# cradle_venus.net
KiCad netlist of a schematic drawn in EAGLE
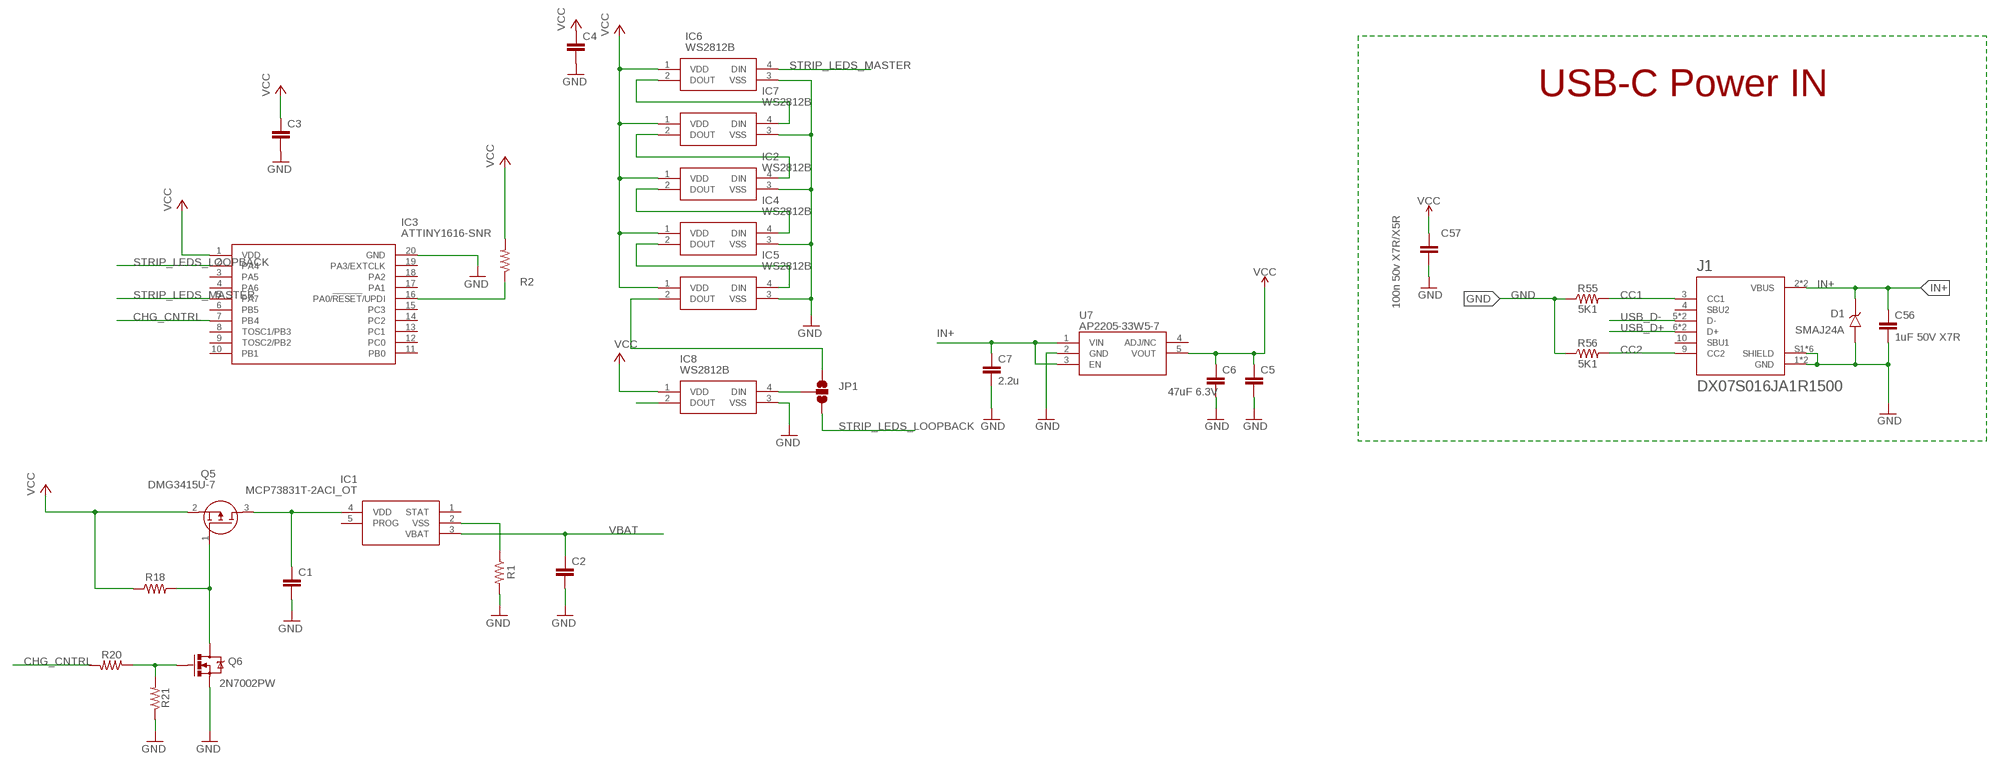
[diagram p0: schematic, sheet 1]

(export (version "E")
  (design (tool "Eeschema 10.0.6"))
  (components
    (comp (ref "C1")
      (value "C-EUC0805")
      (footprint "eagle-import:C0805")
      (libsource (lib "eagle-import") (part "C-EUC0805"))
    )
    (comp (ref "C2")
      (value "C-EUC0805")
      (footprint "eagle-import:C0805")
      (libsource (lib "eagle-import") (part "C-EUC0805"))
    )
    (comp (ref "C3")
      (value "C-EUC0805")
      (footprint "eagle-import:C0805")
      (libsource (lib "eagle-import") (part "C-EUC0805"))
    )
    (comp (ref "C4")
      (value "C-EUC0805")
      (footprint "eagle-import:C0805")
      (libsource (lib "eagle-import") (part "C-EUC0805"))
    )
    (comp (ref "C5")
      (value "C-EUC0805")
      (footprint "eagle-import:C0805")
      (libsource (lib "eagle-import") (part "C-EUC0805"))
    )
    (comp (ref "C6")
      (value "47uF 6.3V")
      (footprint "eagle-import:0603-CAP")
      (libsource (lib "eagle-import") (part "4.7UF-6.3V-10%(0603)0603"))
    )
    (comp (ref "C7")
      (value "2.2u")
      (footprint "eagle-import:0603-CAP")
      (libsource (lib "eagle-import") (part "4.7UF-6.3V-10%(0603)0603"))
    )
    (comp (ref "C56")
      (value "1uF 50V X7R")
      (footprint "eagle-import:0805")
      (libsource (lib "eagle-import") (part "CAP0805"))
    )
    (comp (ref "C57")
      (value "100n 50v X7R/X5R")
      (footprint "eagle-import:0805")
      (libsource (lib "eagle-import") (part "CAP0805"))
    )
    (comp (ref "D1")
      (value "SMAJ24A")
      (footprint "eagle-import:DIOM4325X244N")
      (fields (field (name "MF") "Micro Commercial Components") (field (name "MP") "3SMAJ5934B"))
      (libsource (lib "eagle-import") (part "3SMAJ5934B"))
    )
    (comp (ref "IC1")
      (value "MCP73831T-2ACI_OT")
      (footprint "eagle-import:SOT95P270X145-5N")
      (fields
        (field (name "ARROW_PART_NUMBER") "MCP73831T-2ACI/OT")
        (field (name "MOUSER_PART_NUMBER") "579-MCP73831T-2ACIOT")
      )
      (libsource (lib "eagle-import") (part "MCP73831T-2ACI_OT"))
    )
    (comp (ref "IC2")
      (value "WS2812B")
      (footprint "eagle-import:WS2812B")
      (libsource (lib "eagle-import") (part "WS2812B"))
    )
    (comp (ref "IC3")
      (value "ATTINY1616-SNR")
      (footprint "eagle-import:SOIC127P1030X265-20N")
      (fields (field (name "MOUSER_PART_NUMBER") "556-ATTINY1616SNR"))
      (libsource (lib "eagle-import") (part "ATTINY1616-SNR"))
    )
    (comp (ref "IC4")
      (value "WS2812B")
      (footprint "eagle-import:WS2812B")
      (libsource (lib "eagle-import") (part "WS2812B"))
    )
    (comp (ref "IC5")
      (value "WS2812B")
      (footprint "eagle-import:WS2812B")
      (libsource (lib "eagle-import") (part "WS2812B"))
    )
    (comp (ref "IC6")
      (value "WS2812B")
      (footprint "eagle-import:WS2812B")
      (libsource (lib "eagle-import") (part "WS2812B"))
    )
    (comp (ref "IC7")
      (value "WS2812B")
      (footprint "eagle-import:WS2812B")
      (libsource (lib "eagle-import") (part "WS2812B"))
    )
    (comp (ref "IC8")
      (value "WS2812B")
      (footprint "eagle-import:WS2812B")
      (libsource (lib "eagle-import") (part "WS2812B"))
    )
    (comp (ref "J1")
      (value "DX07S016JA1R1500")
      (footprint "eagle-import:JAE_DX07S016JA1R1500")
      (fields
        (field (name "DIGI-KEY_PART_NUMBER") "670-DX07S016JA1R1500CT-ND")
        (field (name "MF") "JAE Electronics")
      )
      (libsource (lib "eagle-import") (part "DX07S016JA1R1500"))
    )
    (comp (ref "JP1")
      (value "JUMPER-SMT_3_NO_SILK")
      (footprint "eagle-import:SMT-JUMPER_3_NO_SILK")
      (libsource (lib "eagle-import") (part "JUMPER-SMT_3_NO_SILK"))
    )
    (comp (ref "Q5")
      (value "DMG3415U-7")
      (footprint "eagle-import:SSM3J332RLFT")
      (fields
        (field (name "ARROW_PART_NUMBER") "SSM3J338R,LF")
        (field (name "MOUSER_PART_NUMBER") "757-SSM3J338RLF")
      )
      (libsource (lib "eagle-import") (part "SSM3J338R,LF"))
    )
    (comp (ref "Q6")
      (value "2N7002PW")
      (footprint "eagle-import:SOT323")
      (libsource (lib "eagle-import") (part "MOSFET-NCHANNEL2N7002PW"))
    )
    (comp (ref "R1")
      (value "RESISTOR0805")
      (footprint "eagle-import:0805")
      (libsource (lib "eagle-import") (part "RESISTOR0805"))
    )
    (comp (ref "R2")
      (value "RESISTOR0805")
      (footprint "eagle-import:0805")
      (libsource (lib "eagle-import") (part "RESISTOR0805"))
    )
    (comp (ref "R18")
      (value "RESISTOR0805")
      (footprint "eagle-import:0805")
      (libsource (lib "eagle-import") (part "RESISTOR0805"))
    )
    (comp (ref "R20")
      (value "RESISTOR0805")
      (footprint "eagle-import:0805")
      (libsource (lib "eagle-import") (part "RESISTOR0805"))
    )
    (comp (ref "R21")
      (value "RESISTOR0805")
      (footprint "eagle-import:0805")
      (libsource (lib "eagle-import") (part "RESISTOR0805"))
    )
    (comp (ref "R55")
      (value "5K1")
      (footprint "eagle-import:0805")
      (libsource (lib "eagle-import") (part "RESISTOR0805"))
    )
    (comp (ref "R56")
      (value "5K1")
      (footprint "eagle-import:0805")
      (libsource (lib "eagle-import") (part "RESISTOR0805"))
    )
    (comp (ref "U7")
      (value "AP2205-33W5-7")
      (footprint "eagle-import:SOT95P282X145-5N")
      (fields
        (field (name "MANUFACTURER_PART_NUMBER") "AP2205-W5-7")
        (field (name "MOUSER_PART_NUMBER") "621-AP2205-W5-7")
      )
      (libsource (lib "eagle-import") (part "AP2205-W5-7"))
    )
  )
  (nets
    (net (code "1") (name "/CC1") (class "Default")
      (node (ref "J1") (pin "3") (pinfunction "CC1_3") (pintype "passive"))
      (node (ref "R55") (pin "2") (pinfunction "2_2") (pintype "passive"))
    )
    (net (code "2") (name "/CC2") (class "Default")
      (node (ref "J1") (pin "9") (pinfunction "CC2_9") (pintype "passive"))
      (node (ref "R56") (pin "2") (pinfunction "2_2") (pintype "passive"))
    )
    (net (code "3") (name "/CHG_CNTRL") (class "Default")
      (node (ref "IC3") (pin "7") (pinfunction "PB4_7") (pintype "bidirectional"))
      (node (ref "R20") (pin "2") (pinfunction "2_2") (pintype "passive"))
    )
    (net (code "4") (name "/STRIP_LEDS_LOOPBACK") (class "Default")
      (node (ref "IC3") (pin "2") (pinfunction "PA4_2") (pintype "bidirectional"))
      (node (ref "JP1") (pin "3") (pinfunction "3_3") (pintype "passive"))
    )
    (net (code "5") (name "/STRIP_LEDS_MASTER") (class "Default")
      (node (ref "IC3") (pin "5") (pinfunction "PA7_5") (pintype "bidirectional"))
      (node (ref "IC6") (pin "4") (pinfunction "DIN_4") (pintype "bidirectional"))
    )
    (net (code "6") (name "/USB_D+") (class "Default")
      (node (ref "J1") (pin "6") (pinfunction "D+_6") (pintype "passive"))
      (node (ref "J1") (pin "7") (pinfunction "D+_7") (pintype "passive"))
    )
    (net (code "7") (name "/USB_D-") (class "Default")
      (node (ref "J1") (pin "5") (pinfunction "D-_5") (pintype "passive"))
      (node (ref "J1") (pin "8") (pinfunction "D-_8") (pintype "passive"))
    )
    (net (code "8") (name "/VBAT") (class "Default")
      (node (ref "C2") (pin "1") (pinfunction "1_1") (pintype "passive"))
      (node (ref "IC1") (pin "3") (pinfunction "VBAT_3") (pintype "bidirectional"))
    )
    (net (code "9") (name "GND") (class "Default")
      (node (ref "C1") (pin "2") (pinfunction "2_2") (pintype "passive"))
      (node (ref "C2") (pin "2") (pinfunction "2_2") (pintype "passive"))
      (node (ref "C3") (pin "2") (pinfunction "2_2") (pintype "passive"))
      (node (ref "C4") (pin "2") (pinfunction "2_2") (pintype "passive"))
      (node (ref "C5") (pin "2") (pinfunction "2_2") (pintype "passive"))
      (node (ref "C56") (pin "2") (pinfunction "2_2") (pintype "passive"))
      (node (ref "C57") (pin "2") (pinfunction "2_2") (pintype "passive"))
      (node (ref "C6") (pin "2") (pinfunction "2_2") (pintype "passive"))
      (node (ref "C7") (pin "2") (pinfunction "2_2") (pintype "passive"))
      (node (ref "D1") (pin "A") (pinfunction "A_A") (pintype "passive"))
      (node (ref "IC2") (pin "3") (pinfunction "VSS_3") (pintype "bidirectional"))
      (node (ref "IC3") (pin "20") (pinfunction "GND_20") (pintype "bidirectional"))
      (node (ref "IC4") (pin "3") (pinfunction "VSS_3") (pintype "bidirectional"))
      (node (ref "IC5") (pin "3") (pinfunction "VSS_3") (pintype "bidirectional"))
      (node (ref "IC6") (pin "3") (pinfunction "VSS_3") (pintype "bidirectional"))
      (node (ref "IC7") (pin "3") (pinfunction "VSS_3") (pintype "bidirectional"))
      (node (ref "IC8") (pin "3") (pinfunction "VSS_3") (pintype "bidirectional"))
      (node (ref "J1") (pin "1") (pinfunction "GND_1") (pintype "power_in"))
      (node (ref "J1") (pin "12") (pinfunction "GND_12") (pintype "power_in"))
      (node (ref "J1") (pin "S1") (pinfunction "SHIELD_S1") (pintype "passive"))
      (node (ref "J1") (pin "S2") (pinfunction "SHIELD_S2") (pintype "passive"))
      (node (ref "J1") (pin "S3") (pinfunction "SHIELD_S3") (pintype "passive"))
      (node (ref "J1") (pin "S4") (pinfunction "SHIELD_S4") (pintype "passive"))
      (node (ref "J1") (pin "S5") (pinfunction "SHIELD_S5") (pintype "passive"))
      (node (ref "J1") (pin "S6") (pinfunction "SHIELD_S6") (pintype "passive"))
      (node (ref "Q6") (pin "2") (pinfunction "S_2") (pintype "passive"))
      (node (ref "R1") (pin "2") (pinfunction "2_2") (pintype "passive"))
      (node (ref "R21") (pin "1") (pinfunction "1_1") (pintype "passive"))
      (node (ref "R55") (pin "1") (pinfunction "1_1") (pintype "passive"))
      (node (ref "R56") (pin "1") (pinfunction "1_1") (pintype "passive"))
      (node (ref "U7") (pin "2") (pinfunction "GND_2") (pintype "bidirectional"))
    )
    (net (code "10") (name "IN+") (class "Default")
      (node (ref "C56") (pin "1") (pinfunction "1_1") (pintype "passive"))
      (node (ref "C7") (pin "1") (pinfunction "1_1") (pintype "passive"))
      (node (ref "D1") (pin "C") (pinfunction "K_C") (pintype "passive"))
      (node (ref "J1") (pin "11") (pinfunction "VBUS_11") (pintype "power_in"))
      (node (ref "J1") (pin "2") (pinfunction "VBUS_2") (pintype "power_in"))
      (node (ref "U7") (pin "1") (pinfunction "VIN_1") (pintype "bidirectional"))
      (node (ref "U7") (pin "3") (pinfunction "EN_3") (pintype "bidirectional"))
    )
    (net (code "11") (name "Net-(IC1-VDD)") (class "Default")
      (node (ref "C1") (pin "1") (pinfunction "1_1") (pintype "passive"))
      (node (ref "IC1") (pin "4") (pinfunction "VDD_4") (pintype "bidirectional"))
      (node (ref "Q5") (pin "3") (pinfunction "D_3") (pintype "bidirectional"))
    )
    (net (code "12") (name "Net-(IC1-VSS)") (class "Default")
      (node (ref "IC1") (pin "2") (pinfunction "VSS_2") (pintype "bidirectional"))
      (node (ref "R1") (pin "1") (pinfunction "1_1") (pintype "passive"))
    )
    (net (code "13") (name "Net-(IC2-DIN)") (class "Default")
      (node (ref "IC2") (pin "4") (pinfunction "DIN_4") (pintype "bidirectional"))
      (node (ref "IC7") (pin "2") (pinfunction "DOUT_2") (pintype "bidirectional"))
    )
    (net (code "14") (name "Net-(IC2-DOUT)") (class "Default")
      (node (ref "IC2") (pin "2") (pinfunction "DOUT_2") (pintype "bidirectional"))
      (node (ref "IC4") (pin "4") (pinfunction "DIN_4") (pintype "bidirectional"))
    )
    (net (code "15") (name "Net-(IC3-PA0{slash}~{RESET}{slash}UPDI)") (class "Default")
      (node (ref "IC3") (pin "16") (pinfunction "PA0/~{RESET}/UPDI_16") (pintype "bidirectional"))
      (node (ref "R2") (pin "1") (pinfunction "1_1") (pintype "passive"))
    )
    (net (code "16") (name "Net-(IC4-DOUT)") (class "Default")
      (node (ref "IC4") (pin "2") (pinfunction "DOUT_2") (pintype "bidirectional"))
      (node (ref "IC5") (pin "4") (pinfunction "DIN_4") (pintype "bidirectional"))
    )
    (net (code "17") (name "Net-(IC5-DOUT)") (class "Default")
      (node (ref "IC5") (pin "2") (pinfunction "DOUT_2") (pintype "bidirectional"))
      (node (ref "JP1") (pin "1") (pinfunction "1_1") (pintype "passive"))
    )
    (net (code "18") (name "Net-(IC6-DOUT)") (class "Default")
      (node (ref "IC6") (pin "2") (pinfunction "DOUT_2") (pintype "bidirectional"))
      (node (ref "IC7") (pin "4") (pinfunction "DIN_4") (pintype "bidirectional"))
    )
    (net (code "19") (name "Net-(IC8-DIN)") (class "Default")
      (node (ref "IC8") (pin "4") (pinfunction "DIN_4") (pintype "bidirectional"))
      (node (ref "JP1") (pin "2") (pinfunction "2_2") (pintype "passive"))
    )
    (net (code "20") (name "Net-(Q5-G)") (class "Default")
      (node (ref "Q5") (pin "1") (pinfunction "G_1") (pintype "bidirectional"))
      (node (ref "Q6") (pin "3") (pinfunction "D_3") (pintype "passive"))
      (node (ref "R18") (pin "2") (pinfunction "2_2") (pintype "passive"))
    )
    (net (code "21") (name "Net-(Q6-G)") (class "Default")
      (node (ref "Q6") (pin "1") (pinfunction "G_1") (pintype "passive"))
      (node (ref "R20") (pin "1") (pinfunction "1_1") (pintype "passive"))
      (node (ref "R21") (pin "2") (pinfunction "2_2") (pintype "passive"))
    )
    (net (code "22") (name "VCC") (class "Default")
      (node (ref "C3") (pin "1") (pinfunction "1_1") (pintype "passive"))
      (node (ref "C4") (pin "1") (pinfunction "1_1") (pintype "passive"))
      (node (ref "C5") (pin "1") (pinfunction "1_1") (pintype "passive"))
      (node (ref "C57") (pin "1") (pinfunction "1_1") (pintype "passive"))
      (node (ref "C6") (pin "1") (pinfunction "1_1") (pintype "passive"))
      (node (ref "IC2") (pin "1") (pinfunction "VDD_1") (pintype "bidirectional"))
      (node (ref "IC3") (pin "1") (pinfunction "VDD_1") (pintype "bidirectional"))
      (node (ref "IC4") (pin "1") (pinfunction "VDD_1") (pintype "bidirectional"))
      (node (ref "IC5") (pin "1") (pinfunction "VDD_1") (pintype "bidirectional"))
      (node (ref "IC6") (pin "1") (pinfunction "VDD_1") (pintype "bidirectional"))
      (node (ref "IC7") (pin "1") (pinfunction "VDD_1") (pintype "bidirectional"))
      (node (ref "IC8") (pin "1") (pinfunction "VDD_1") (pintype "bidirectional"))
      (node (ref "Q5") (pin "2") (pinfunction "S_2") (pintype "bidirectional"))
      (node (ref "R18") (pin "1") (pinfunction "1_1") (pintype "passive"))
      (node (ref "R2") (pin "2") (pinfunction "2_2") (pintype "passive"))
      (node (ref "U7") (pin "5") (pinfunction "VOUT_5") (pintype "bidirectional"))
    )
    (net (code "23") (name "unconnected-(IC1-PROG-Pad5)") (class "Default")
      (node (ref "IC1") (pin "5") (pinfunction "PROG_5") (pintype "bidirectional"))
    )
    (net (code "24") (name "unconnected-(IC1-STAT-Pad1)") (class "Default")
      (node (ref "IC1") (pin "1") (pinfunction "STAT_1") (pintype "bidirectional"))
    )
    (net (code "25") (name "unconnected-(IC3-PA1-Pad17)") (class "Default")
      (node (ref "IC3") (pin "17") (pinfunction "PA1_17") (pintype "bidirectional"))
    )
    (net (code "26") (name "unconnected-(IC3-PA2-Pad18)") (class "Default")
      (node (ref "IC3") (pin "18") (pinfunction "PA2_18") (pintype "bidirectional"))
    )
    (net (code "27") (name "unconnected-(IC3-PA3{slash}EXTCLK-Pad19)") (class "Default")
      (node (ref "IC3") (pin "19") (pinfunction "PA3/EXTCLK_19") (pintype "bidirectional"))
    )
    (net (code "28") (name "unconnected-(IC3-PA5-Pad3)") (class "Default")
      (node (ref "IC3") (pin "3") (pinfunction "PA5_3") (pintype "bidirectional"))
    )
    (net (code "29") (name "unconnected-(IC3-PA6-Pad4)") (class "Default")
      (node (ref "IC3") (pin "4") (pinfunction "PA6_4") (pintype "bidirectional"))
    )
    (net (code "30") (name "unconnected-(IC3-PB0-Pad11)") (class "Default")
      (node (ref "IC3") (pin "11") (pinfunction "PB0_11") (pintype "bidirectional"))
    )
    (net (code "31") (name "unconnected-(IC3-PB1-Pad10)") (class "Default")
      (node (ref "IC3") (pin "10") (pinfunction "PB1_10") (pintype "bidirectional"))
    )
    (net (code "32") (name "unconnected-(IC3-PB5-Pad6)") (class "Default")
      (node (ref "IC3") (pin "6") (pinfunction "PB5_6") (pintype "bidirectional"))
    )
    (net (code "33") (name "unconnected-(IC3-PC0-Pad12)") (class "Default")
      (node (ref "IC3") (pin "12") (pinfunction "PC0_12") (pintype "bidirectional"))
    )
    (net (code "34") (name "unconnected-(IC3-PC1-Pad13)") (class "Default")
      (node (ref "IC3") (pin "13") (pinfunction "PC1_13") (pintype "bidirectional"))
    )
    (net (code "35") (name "unconnected-(IC3-PC2-Pad14)") (class "Default")
      (node (ref "IC3") (pin "14") (pinfunction "PC2_14") (pintype "bidirectional"))
    )
    (net (code "36") (name "unconnected-(IC3-PC3-Pad15)") (class "Default")
      (node (ref "IC3") (pin "15") (pinfunction "PC3_15") (pintype "bidirectional"))
    )
    (net (code "37") (name "unconnected-(IC3-TOSC1{slash}PB3-Pad8)") (class "Default")
      (node (ref "IC3") (pin "8") (pinfunction "TOSC1/PB3_8") (pintype "bidirectional"))
    )
    (net (code "38") (name "unconnected-(IC3-TOSC2{slash}PB2-Pad9)") (class "Default")
      (node (ref "IC3") (pin "9") (pinfunction "TOSC2/PB2_9") (pintype "bidirectional"))
    )
    (net (code "39") (name "unconnected-(IC8-DOUT-Pad2)") (class "Default")
      (node (ref "IC8") (pin "2") (pinfunction "DOUT_2") (pintype "bidirectional"))
    )
    (net (code "40") (name "unconnected-(J1-SBU1-Pad10)") (class "Default")
      (node (ref "J1") (pin "10") (pinfunction "SBU1_10") (pintype "passive"))
    )
    (net (code "41") (name "unconnected-(J1-SBU2-Pad4)") (class "Default")
      (node (ref "J1") (pin "4") (pinfunction "SBU2_4") (pintype "passive"))
    )
    (net (code "42") (name "unconnected-(U7-ADJ{slash}NC-Pad4)") (class "Default")
      (node (ref "U7") (pin "4") (pinfunction "ADJ/NC_4") (pintype "bidirectional"))
    )
  )
)
